# compare3_2.net
KiCad netlist of a schematic drawn in EAGLE
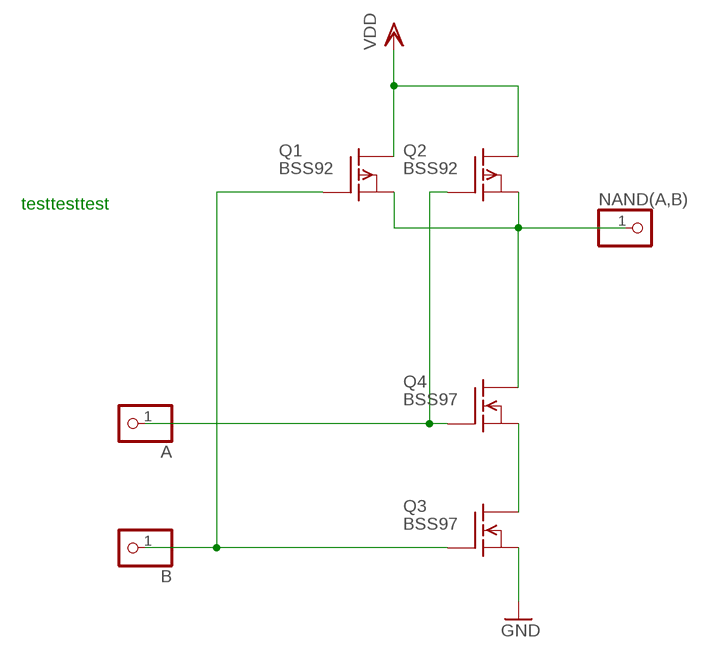
[diagram p0: schematic, sheet 1]

(export (version "E")
  (design (tool "Eeschema 10.0.6"))
  (components
    (comp (ref "A")
      (value "PINHD-1X1")
      (footprint "eagle-import:1X01")
      (libsource (lib "eagle-import") (part "PINHD-1X1"))
    )
    (comp (ref "B")
      (value "PINHD-1X1")
      (footprint "eagle-import:1X01")
      (libsource (lib "eagle-import") (part "PINHD-1X1"))
    )
    (comp (ref "NAND(A,B)")
      (value "PINHD-1X1")
      (footprint "eagle-import:1X01")
      (libsource (lib "eagle-import") (part "PINHD-1X1"))
    )
    (comp (ref "Q1")
      (value "BSS92")
      (footprint "eagle-import:TO92")
      (libsource (lib "eagle-import") (part "BSS92"))
    )
    (comp (ref "Q2")
      (value "BSS92")
      (footprint "eagle-import:TO92")
      (libsource (lib "eagle-import") (part "BSS92"))
    )
    (comp (ref "Q3")
      (value "BSS97")
      (footprint "eagle-import:TO202")
      (libsource (lib "eagle-import") (part "BSS97"))
    )
    (comp (ref "Q4")
      (value "BSS97")
      (footprint "eagle-import:TO202")
      (libsource (lib "eagle-import") (part "BSS97"))
    )
  )
  (nets
    (net (code "1") (name "GND") (class "Default")
      (node (ref "Q3") (pin "1") (pinfunction "S_1") (pintype "passive"))
    )
    (net (code "2") (name "Net-(Q1-G)") (class "Default")
      (node (ref "B") (pin "1") (pinfunction "1_1") (pintype "passive"))
      (node (ref "Q1") (pin "1") (pinfunction "G_1") (pintype "passive"))
      (node (ref "Q3") (pin "3") (pinfunction "G_3") (pintype "passive"))
    )
    (net (code "3") (name "Net-(Q1-S)") (class "Default")
      (node (ref "NAND(A,B)") (pin "1") (pinfunction "1_1") (pintype "passive"))
      (node (ref "Q1") (pin "3") (pinfunction "S_3") (pintype "passive"))
      (node (ref "Q2") (pin "3") (pinfunction "S_3") (pintype "passive"))
      (node (ref "Q4") (pin "2") (pinfunction "D_2") (pintype "passive"))
    )
    (net (code "4") (name "Net-(Q2-G)") (class "Default")
      (node (ref "A") (pin "1") (pinfunction "1_1") (pintype "passive"))
      (node (ref "Q2") (pin "1") (pinfunction "G_1") (pintype "passive"))
      (node (ref "Q4") (pin "3") (pinfunction "G_3") (pintype "passive"))
    )
    (net (code "5") (name "Net-(Q3-D)") (class "Default")
      (node (ref "Q3") (pin "2") (pinfunction "D_2") (pintype "passive"))
      (node (ref "Q4") (pin "1") (pinfunction "S_1") (pintype "passive"))
    )
    (net (code "6") (name "VDD") (class "Default")
      (node (ref "Q1") (pin "2") (pinfunction "D_2") (pintype "passive"))
      (node (ref "Q2") (pin "2") (pinfunction "D_2") (pintype "passive"))
    )
  )
)
